# Enclosure_100x68_BPS.net
KiCad netlist of a schematic drawn in EAGLE
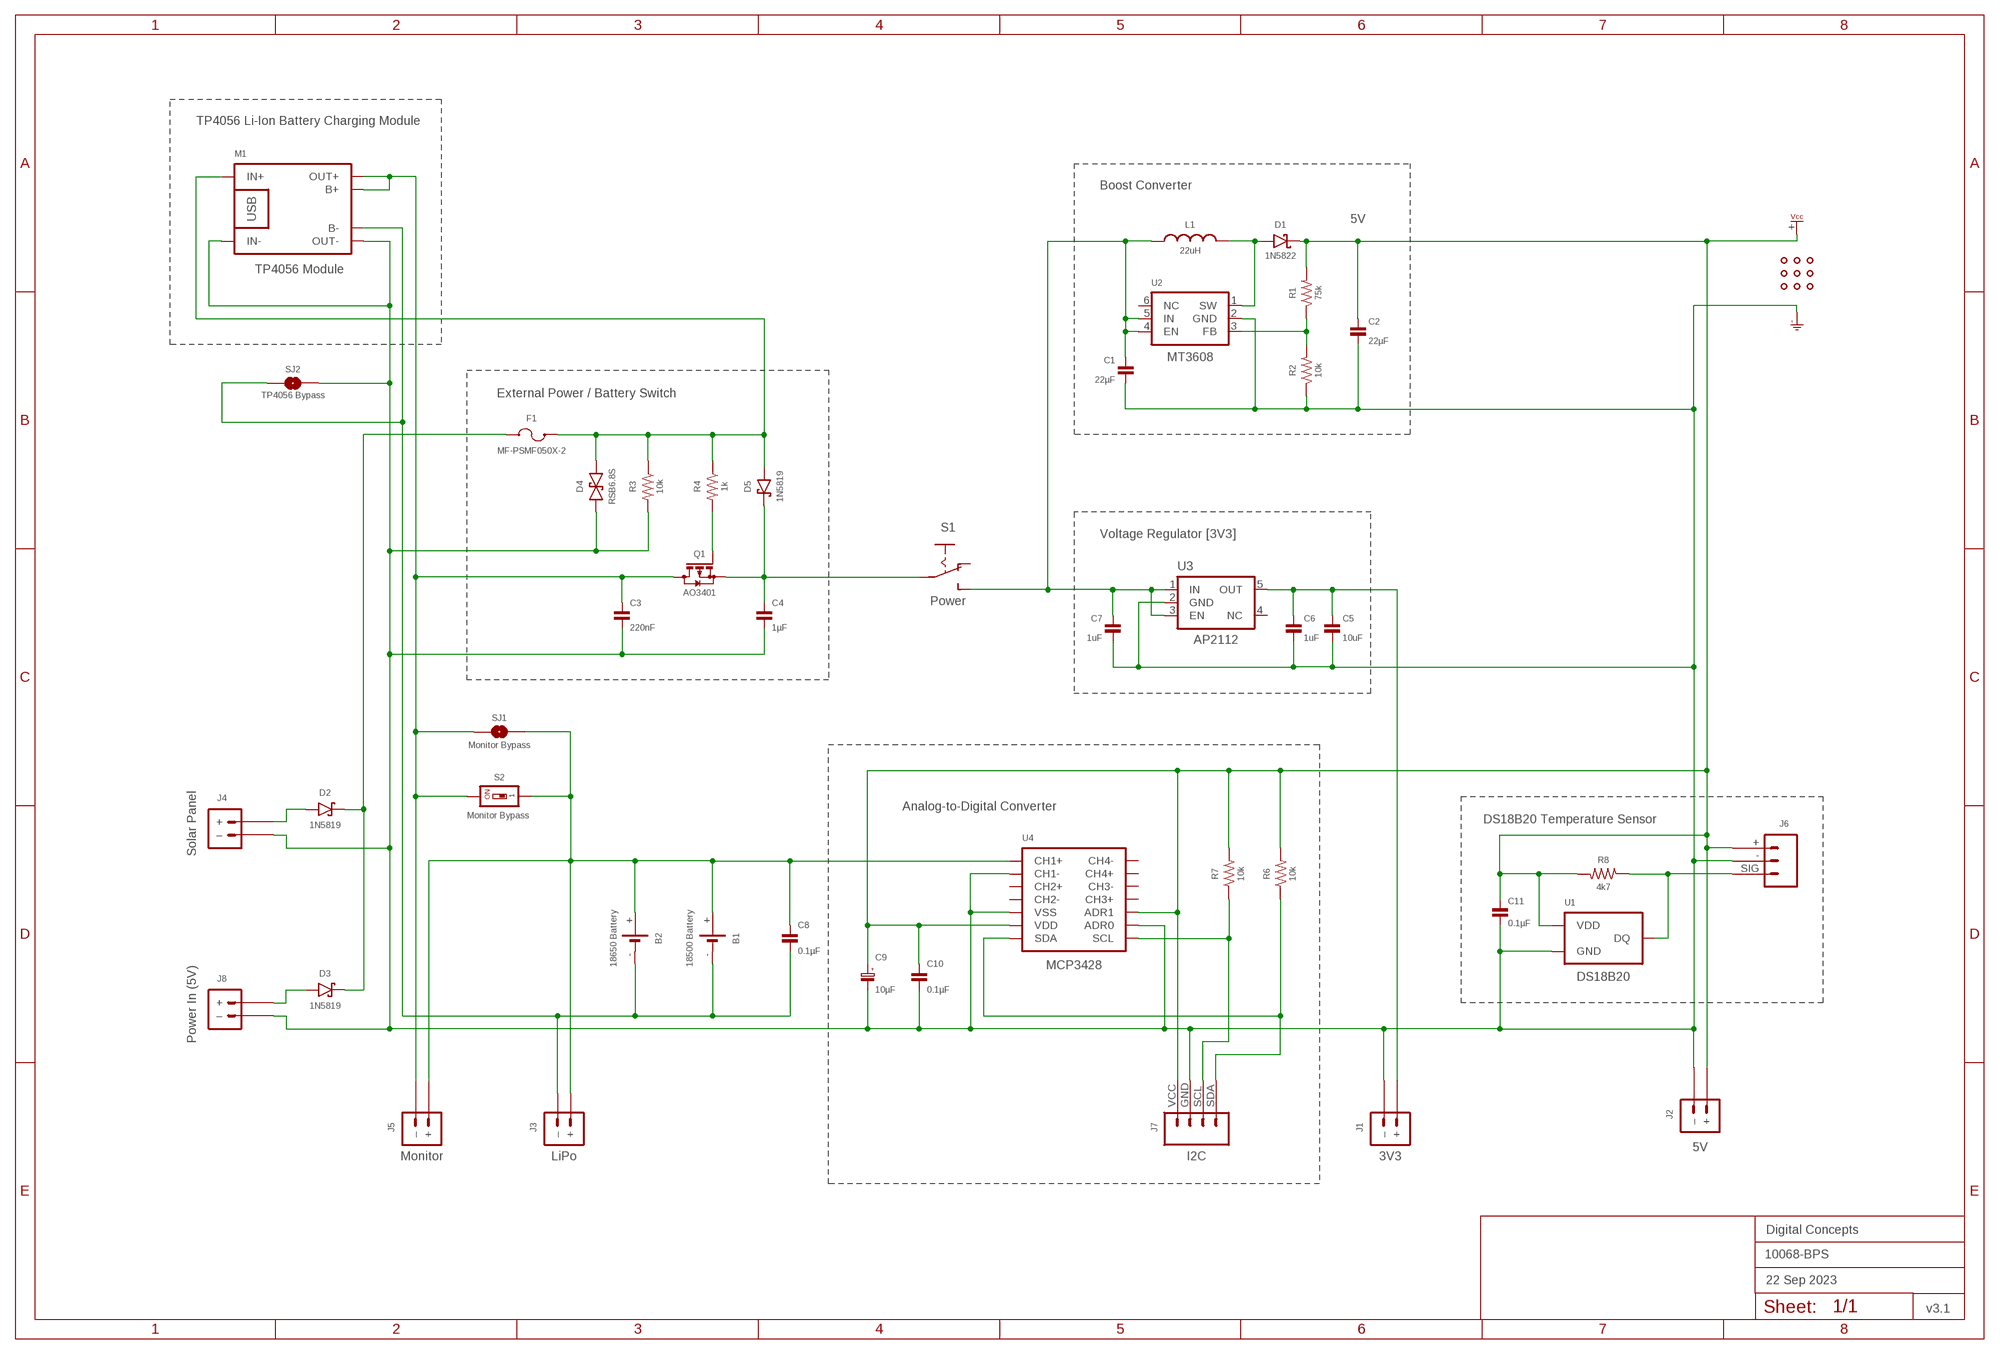
[diagram p0: schematic, sheet 1]

(export (version "E")
  (design (tool "Eeschema 10.0.6"))
  (components
    (comp (ref "B1")
      (value "18500 Battery")
      (footprint "eagle-import:BATTERY-18500")
      (libsource (lib "eagle-import") (part "BATTERY-HOLDER-18500"))
    )
    (comp (ref "B2")
      (value "18650 Battery")
      (footprint "eagle-import:BATTERY-18650")
      (libsource (lib "eagle-import") (part "BATTERY-HOLDER-18650"))
    )
    (comp (ref "C1")
      (value "22µF")
      (footprint "eagle-import:C1206")
      (libsource (lib "eagle-import") (part "CAPACITOR-1206"))
    )
    (comp (ref "C2")
      (value "22µF")
      (footprint "eagle-import:C1206")
      (libsource (lib "eagle-import") (part "CAPACITOR-1206"))
    )
    (comp (ref "C3")
      (value "220nF")
      (footprint "eagle-import:C0805")
      (libsource (lib "eagle-import") (part "CAPACITOR-0805"))
    )
    (comp (ref "C4")
      (value "1µF")
      (footprint "eagle-import:C0805")
      (libsource (lib "eagle-import") (part "CAPACITOR-0805"))
    )
    (comp (ref "C5")
      (value "10uF")
      (footprint "eagle-import:C0805")
      (libsource (lib "eagle-import") (part "CAPACITOR-0805"))
    )
    (comp (ref "C6")
      (value "1uF")
      (footprint "eagle-import:C0805")
      (libsource (lib "eagle-import") (part "CAPACITOR-0805"))
    )
    (comp (ref "C7")
      (value "1uF")
      (footprint "eagle-import:C0805")
      (libsource (lib "eagle-import") (part "CAPACITOR-0805"))
    )
    (comp (ref "C8")
      (value "0.1µF")
      (footprint "eagle-import:C0805")
      (libsource (lib "eagle-import") (part "CAPACITOR-0805"))
    )
    (comp (ref "C9")
      (value "10µF")
      (footprint "eagle-import:C1206-POLARISED")
      (libsource (lib "eagle-import") (part "CAPACITOR-1206-TANTALUM"))
    )
    (comp (ref "C10")
      (value "0.1µF")
      (footprint "eagle-import:C0805")
      (libsource (lib "eagle-import") (part "CAPACITOR-0805"))
    )
    (comp (ref "C11")
      (value "0.1µF")
      (footprint "eagle-import:C0805")
      (libsource (lib "eagle-import") (part "CAPACITOR-0805"))
    )
    (comp (ref "D1")
      (value "1N5822")
      (footprint "eagle-import:DIODE_SMB")
      (libsource (lib "eagle-import") (part "DIODE-SCHOTTKY-1N5822"))
    )
    (comp (ref "D2")
      (value "1N5819")
      (footprint "eagle-import:SOD-123")
      (libsource (lib "eagle-import") (part "DIODE-SCHOTTKY-1N5819"))
    )
    (comp (ref "D3")
      (value "1N5819")
      (footprint "eagle-import:SOD-123")
      (libsource (lib "eagle-import") (part "DIODE-SCHOTTKY-1N5819"))
    )
    (comp (ref "D4")
      (value "RSB6.8S")
      (footprint "eagle-import:EMD2")
      (libsource (lib "eagle-import") (part "DIODE-BIDIRECTIONAL-RSB6.8S"))
    )
    (comp (ref "D5")
      (value "1N5819")
      (footprint "eagle-import:SOD-123")
      (libsource (lib "eagle-import") (part "DIODE-SCHOTTKY-1N5819"))
    )
    (comp (ref "F1")
      (value "MF-PSMF050X-2")
      (footprint "eagle-import:F0805")
      (libsource (lib "eagle-import") (part "MF-PSMF050X-2"))
    )
    (comp (ref "J1")
      (value "3V3")
      (footprint "eagle-import:JST-PH2.0-2-VERTICAL-POWER")
      (libsource (lib "eagle-import") (part "JST-PH2.0-2-VERTICAL-POWER"))
    )
    (comp (ref "J2")
      (value "5V")
      (footprint "eagle-import:JST-PH2.0-2-VERTICAL-POWER")
      (libsource (lib "eagle-import") (part "JST-PH2.0-2-VERTICAL-POWER"))
    )
    (comp (ref "J3")
      (value "LiPo")
      (footprint "eagle-import:JST-PH2.0-2-HORIZONTAL-POWER")
      (libsource (lib "eagle-import") (part "JST-PH2.0-2-HORIZONTAL-POWERJST-PTH-2"))
    )
    (comp (ref "J4")
      (value "Solar Panel")
      (footprint "eagle-import:JST-PH2.0-2-VERTICAL-POWER")
      (libsource (lib "eagle-import") (part "JST-PH2.0-2-VERTICAL-POWER"))
    )
    (comp (ref "J5")
      (value "Monitor")
      (footprint "eagle-import:JST-PH2.0-2-VERTICAL-POWER")
      (libsource (lib "eagle-import") (part "JST-PH2.0-2-VERTICAL-POWER"))
    )
    (comp (ref "J6")
      (value "JST-PH2.0-3-HORIZONTAL-DS18B20")
      (footprint "eagle-import:JST-PH2.0-3-HORIZONTAL-DS18B20")
      (libsource (lib "eagle-import") (part "JST-PH2.0-3-HORIZONTAL-DS18B20"))
    )
    (comp (ref "J7")
      (value "I2C")
      (footprint "eagle-import:JST-PH2.0-4-HORIZONTAL-I2C")
      (libsource (lib "eagle-import") (part "JST-PH2.0-4-HORIZONTAL-I2C"))
    )
    (comp (ref "J8")
      (value "Power In (5V)")
      (footprint "eagle-import:JST-GH1.25-2-HORIZONTAL")
      (libsource (lib "eagle-import") (part "JST-GH1.25-2-HORIZONTAL-POWER"))
    )
    (comp (ref "L1")
      (value "22uH")
      (footprint "eagle-import:CDRH104R+")
      (libsource (lib "eagle-import") (part "INDUCTOR-CDRH104R+L5038P"))
    )
    (comp (ref "M1")
      (value "TP4056 Module")
      (footprint "eagle-import:BATTERY-CHARGER-LI-PROT")
      (libsource (lib "eagle-import") (part "BATTERY-CHARGER-LI-PROT"))
    )
    (comp (ref "Q1")
      (value "AO3401")
      (footprint "eagle-import:SOT-23")
      (libsource (lib "eagle-import") (part "MOSFET-AO3401"))
    )
    (comp (ref "R1")
      (value "75k")
      (footprint "eagle-import:R0805")
      (libsource (lib "eagle-import") (part "RESISTORR0805"))
    )
    (comp (ref "R2")
      (value "10k")
      (footprint "eagle-import:R0805")
      (libsource (lib "eagle-import") (part "RESISTORR0805"))
    )
    (comp (ref "R3")
      (value "10k")
      (footprint "eagle-import:R0805")
      (libsource (lib "eagle-import") (part "RESISTORR0805"))
    )
    (comp (ref "R4")
      (value "1k")
      (footprint "eagle-import:R0805")
      (libsource (lib "eagle-import") (part "RESISTORR0805"))
    )
    (comp (ref "R6")
      (value "10k")
      (footprint "eagle-import:R0805")
      (libsource (lib "eagle-import") (part "RESISTORR0805"))
    )
    (comp (ref "R7")
      (value "10k")
      (footprint "eagle-import:R0805")
      (libsource (lib "eagle-import") (part "RESISTORR0805"))
    )
    (comp (ref "R8")
      (value "4k7")
      (footprint "eagle-import:R0805")
      (libsource (lib "eagle-import") (part "RESISTORR0805"))
    )
    (comp (ref "S1")
      (value "Power")
      (footprint "eagle-import:SWITCH-SPDT-PTH")
      (libsource (lib "eagle-import") (part "SWITCH-SLIDE-SPDT-PTH"))
    )
    (comp (ref "S2")
      (value "Monitor Bypass")
      (footprint "eagle-import:SMD-001-VIA-1")
      (libsource (lib "eagle-import") (part "SWITCH-DIP-SWS001-VIA-1"))
    )
    (comp (ref "SJ1")
      (value "Monitor Bypass")
      (footprint "eagle-import:SJ")
      (libsource (lib "eagle-import") (part "SJ"))
    )
    (comp (ref "SJ2")
      (value "TP4056 Bypass")
      (footprint "eagle-import:SJ")
      (libsource (lib "eagle-import") (part "SJ"))
    )
    (comp (ref "U$1")
      (value "PROTO-34X22-PI-CUT")
      (footprint "eagle-import:PROTO-34X22-PI-CUT")
      (libsource (lib "eagle-import") (part "PROTO-34X22-PI-CUT"))
    )
    (comp (ref "U1")
      (value "DS18B20")
      (footprint "eagle-import:TO-92")
      (fields (field (name "MF") "Maxim Integrated"))
      (libsource (lib "eagle-import") (part "THERMOMETER-DS18B20"))
    )
    (comp (ref "U2")
      (value "MT3608")
      (footprint "eagle-import:SOT-23-6")
      (libsource (lib "eagle-import") (part "MT3608"))
    )
    (comp (ref "U3")
      (value "AP2112")
      (footprint "eagle-import:SOT25")
      (libsource (lib "eagle-import") (part "REGULATOR-AP2112"))
    )
    (comp (ref "U4")
      (value "MCP3428")
      (footprint "eagle-import:SOIC-14")
      (libsource (lib "eagle-import") (part "MCP3428"))
    )
  )
  (nets
    (net (code "1") (name "Net-(C9-+)") (class "Default")
      (node (ref "C10") (pin "1") (pinfunction "1_1") (pintype "passive"))
      (node (ref "C11") (pin "1") (pinfunction "1_1") (pintype "passive"))
      (node (ref "C2") (pin "1") (pinfunction "1_1") (pintype "passive"))
      (node (ref "C9") (pin "1") (pinfunction "+_1") (pintype "passive"))
      (node (ref "D1") (pin "C") (pinfunction "C_C") (pintype "passive"))
      (node (ref "J2") (pin "+") (pinfunction "+_+") (pintype "power_in"))
      (node (ref "J6") (pin "+") (pinfunction "3_+") (pintype "passive"))
      (node (ref "J7") (pin "VCC") (pinfunction "1_VCC") (pintype "passive"))
      (node (ref "R1") (pin "2") (pinfunction "2_2") (pintype "passive"))
      (node (ref "R6") (pin "2") (pinfunction "2_2") (pintype "passive"))
      (node (ref "R7") (pin "2") (pinfunction "2_2") (pintype "passive"))
      (node (ref "R8") (pin "2") (pinfunction "2_2") (pintype "passive"))
      (node (ref "U$1") (pin "+") (pinfunction "VCC_+") (pintype "power_in"))
      (node (ref "U1") (pin "3") (pinfunction "VDD_3") (pintype "power_in"))
      (node (ref "U4") (pin "P$10") (pinfunction "ADR1_P$10") (pintype "bidirectional"))
      (node (ref "U4") (pin "P$6") (pinfunction "VDD_P$6") (pintype "bidirectional"))
    )
    (net (code "2") (name "Net-(C9--)") (class "Default")
      (node (ref "C1") (pin "2") (pinfunction "2_2") (pintype "passive"))
      (node (ref "C10") (pin "2") (pinfunction "2_2") (pintype "passive"))
      (node (ref "C11") (pin "2") (pinfunction "2_2") (pintype "passive"))
      (node (ref "C2") (pin "2") (pinfunction "2_2") (pintype "passive"))
      (node (ref "C3") (pin "2") (pinfunction "2_2") (pintype "passive"))
      (node (ref "C4") (pin "2") (pinfunction "2_2") (pintype "passive"))
      (node (ref "C5") (pin "2") (pinfunction "2_2") (pintype "passive"))
      (node (ref "C6") (pin "2") (pinfunction "2_2") (pintype "passive"))
      (node (ref "C7") (pin "2") (pinfunction "2_2") (pintype "passive"))
      (node (ref "C9") (pin "2") (pinfunction "-_2") (pintype "passive"))
      (node (ref "D4") (pin "P$2") (pinfunction "2_P$2") (pintype "passive"))
      (node (ref "J1") (pin "-") (pinfunction "–_-") (pintype "power_in"))
      (node (ref "J2") (pin "-") (pinfunction "–_-") (pintype "power_in"))
      (node (ref "J4") (pin "-") (pinfunction "–_-") (pintype "power_in"))
      (node (ref "J6") (pin "-") (pinfunction "2_-") (pintype "passive"))
      (node (ref "J7") (pin "GND") (pinfunction "2_GND") (pintype "passive"))
      (node (ref "J8") (pin "-") (pinfunction "–_-") (pintype "power_in"))
      (node (ref "M1") (pin "IN-") (pinfunction "IN-_IN-") (pintype "power_in"))
      (node (ref "M1") (pin "OUT-") (pinfunction "OUT-_OUT-") (pintype "power_in"))
      (node (ref "R2") (pin "1") (pinfunction "1_1") (pintype "passive"))
      (node (ref "R3") (pin "2") (pinfunction "2_2") (pintype "passive"))
      (node (ref "SJ2") (pin "1") (pinfunction "1_1") (pintype "passive"))
      (node (ref "U$1") (pin "-") (pinfunction "GND_-") (pintype "power_in"))
      (node (ref "U1") (pin "1") (pinfunction "GND_1") (pintype "power_in"))
      (node (ref "U2") (pin "2") (pinfunction "GND_2") (pintype "power_in"))
      (node (ref "U3") (pin "2") (pinfunction "GND_2") (pintype "power_in"))
      (node (ref "U4") (pin "P$2") (pinfunction "CH1-_P$2") (pintype "bidirectional"))
      (node (ref "U4") (pin "P$5") (pinfunction "VSS_P$5") (pintype "bidirectional"))
      (node (ref "U4") (pin "P$9") (pinfunction "ADR0_P$9") (pintype "bidirectional"))
    )
    (net (code "3") (name "Net-(D2-PadA)") (class "Default")
      (node (ref "D2") (pin "A") (pinfunction "A_A") (pintype "passive"))
      (node (ref "J4") (pin "+") (pinfunction "+_+") (pintype "power_in"))
    )
    (net (code "4") (name "Net-(D2-PadC)") (class "Default")
      (node (ref "D2") (pin "C") (pinfunction "C_C") (pintype "passive"))
      (node (ref "D3") (pin "C") (pinfunction "C_C") (pintype "passive"))
      (node (ref "F1") (pin "1") (pinfunction "1_1") (pintype "passive"))
    )
    (net (code "5") (name "Net-(D3-PadA)") (class "Default")
      (node (ref "D3") (pin "A") (pinfunction "A_A") (pintype "passive"))
      (node (ref "J8") (pin "+") (pinfunction "+_+") (pintype "power_in"))
    )
    (net (code "6") (name "Net-(D4-1)") (class "Default")
      (node (ref "D4") (pin "P$1") (pinfunction "1_P$1") (pintype "passive"))
      (node (ref "D5") (pin "A") (pinfunction "A_A") (pintype "passive"))
      (node (ref "F1") (pin "2") (pinfunction "2_2") (pintype "passive"))
      (node (ref "M1") (pin "IN+") (pinfunction "IN+_IN+") (pintype "power_in"))
      (node (ref "R3") (pin "1") (pinfunction "1_1") (pintype "passive"))
      (node (ref "R4") (pin "1") (pinfunction "1_1") (pintype "passive"))
    )
    (net (code "7") (name "Net-(J3-–)") (class "Default")
      (node (ref "B1") (pin "-") (pinfunction "-_-") (pintype "power_in"))
      (node (ref "B2") (pin "-") (pinfunction "-_-") (pintype "power_in"))
      (node (ref "C8") (pin "2") (pinfunction "2_2") (pintype "passive"))
      (node (ref "J3") (pin "-") (pinfunction "–_-") (pintype "power_in"))
      (node (ref "M1") (pin "B-") (pinfunction "B-_B-") (pintype "power_in"))
      (node (ref "SJ2") (pin "2") (pinfunction "2_2") (pintype "passive"))
    )
    (net (code "8") (name "Net-(J5-–)") (class "Default")
      (node (ref "C3") (pin "1") (pinfunction "1_1") (pintype "passive"))
      (node (ref "J5") (pin "-") (pinfunction "–_-") (pintype "power_in"))
      (node (ref "M1") (pin "B+") (pinfunction "B+_B+") (pintype "power_in"))
      (node (ref "M1") (pin "OUT+") (pinfunction "OUT+_OUT+") (pintype "power_in"))
      (node (ref "Q1") (pin "3") (pinfunction "D_3") (pintype "passive"))
      (node (ref "S2") (pin "2") (pinfunction "2_2") (pintype "passive"))
      (node (ref "SJ1") (pin "2") (pinfunction "2_2") (pintype "passive"))
    )
    (net (code "9") (name "Net-(J6-1)") (class "Default")
      (node (ref "J6") (pin "SIG") (pinfunction "1_SIG") (pintype "passive"))
      (node (ref "R8") (pin "1") (pinfunction "1_1") (pintype "passive"))
      (node (ref "U1") (pin "2") (pinfunction "DQ_2") (pintype "bidirectional"))
    )
    (net (code "10") (name "Net-(J7-3)") (class "Default")
      (node (ref "J7") (pin "SCL") (pinfunction "3_SCL") (pintype "passive"))
      (node (ref "R7") (pin "1") (pinfunction "1_1") (pintype "passive"))
      (node (ref "U4") (pin "P$8") (pinfunction "SCL_P$8") (pintype "bidirectional"))
    )
    (net (code "11") (name "Net-(J7-4)") (class "Default")
      (node (ref "J7") (pin "SDA") (pinfunction "4_SDA") (pintype "passive"))
      (node (ref "R6") (pin "1") (pinfunction "1_1") (pintype "passive"))
      (node (ref "U4") (pin "P$7") (pinfunction "SDA_P$7") (pintype "bidirectional"))
    )
    (net (code "12") (name "Net-(Q1-G)") (class "Default")
      (node (ref "Q1") (pin "1") (pinfunction "G_1") (pintype "passive"))
      (node (ref "R4") (pin "2") (pinfunction "2_2") (pintype "passive"))
    )
    (net (code "13") (name "Net-(Q1-S)") (class "Default")
      (node (ref "C4") (pin "1") (pinfunction "1_1") (pintype "passive"))
      (node (ref "D5") (pin "C") (pinfunction "C_C") (pintype "passive"))
      (node (ref "Q1") (pin "2") (pinfunction "S_2") (pintype "passive"))
      (node (ref "S1") (pin "2") (pinfunction "P_2") (pintype "passive"))
    )
    (net (code "14") (name "Net-(S1-S)") (class "Default")
      (node (ref "C1") (pin "1") (pinfunction "1_1") (pintype "passive"))
      (node (ref "C7") (pin "1") (pinfunction "1_1") (pintype "passive"))
      (node (ref "L1") (pin "2") (pinfunction "2_2") (pintype "passive"))
      (node (ref "S1") (pin "3") (pinfunction "S_3") (pintype "passive"))
      (node (ref "U2") (pin "4") (pinfunction "EN_4") (pintype "input"))
      (node (ref "U2") (pin "5") (pinfunction "IN_5") (pintype "power_in"))
      (node (ref "U3") (pin "1") (pinfunction "IN_1") (pintype "power_in"))
      (node (ref "U3") (pin "3") (pinfunction "EN_3") (pintype "input"))
    )
    (net (code "15") (name "Net-(U2-FB)") (class "Default")
      (node (ref "R1") (pin "1") (pinfunction "1_1") (pintype "passive"))
      (node (ref "R2") (pin "2") (pinfunction "2_2") (pintype "passive"))
      (node (ref "U2") (pin "3") (pinfunction "FB_3") (pintype "input"))
    )
    (net (code "16") (name "Net-(U2-SW)") (class "Default")
      (node (ref "D1") (pin "A") (pinfunction "A_A") (pintype "passive"))
      (node (ref "L1") (pin "1") (pinfunction "1_1") (pintype "passive"))
      (node (ref "U2") (pin "1") (pinfunction "SW_1") (pintype "power_in"))
    )
    (net (code "17") (name "Net-(U3-OUT)") (class "Default")
      (node (ref "C5") (pin "1") (pinfunction "1_1") (pintype "passive"))
      (node (ref "C6") (pin "1") (pinfunction "1_1") (pintype "passive"))
      (node (ref "J1") (pin "+") (pinfunction "+_+") (pintype "power_in"))
      (node (ref "U3") (pin "5") (pinfunction "OUT_5") (pintype "power_in"))
    )
    (net (code "18") (name "Net-(U4-CH1+)") (class "Default")
      (node (ref "B1") (pin "+") (pinfunction "+_+") (pintype "power_in"))
      (node (ref "B2") (pin "+") (pinfunction "+_+") (pintype "power_in"))
      (node (ref "C8") (pin "1") (pinfunction "1_1") (pintype "passive"))
      (node (ref "J3") (pin "+") (pinfunction "+_+") (pintype "power_in"))
      (node (ref "J5") (pin "+") (pinfunction "+_+") (pintype "power_in"))
      (node (ref "S2") (pin "1") (pinfunction "1_1") (pintype "passive"))
      (node (ref "S2") (pin "1@VIA") (pinfunction "1_1@VIA") (pintype "passive"))
      (node (ref "SJ1") (pin "1") (pinfunction "1_1") (pintype "passive"))
      (node (ref "U4") (pin "P$1") (pinfunction "CH1+_P$1") (pintype "bidirectional"))
    )
    (net (code "19") (name "unconnected-(S1-O-Pad1)") (class "Default")
      (node (ref "S1") (pin "1") (pinfunction "O_1") (pintype "passive"))
    )
    (net (code "20") (name "unconnected-(U2-NC-Pad6)") (class "Default")
      (node (ref "U2") (pin "6") (pinfunction "NC_6") (pintype "no_connect"))
    )
    (net (code "21") (name "unconnected-(U3-NC-Pad4)") (class "Default")
      (node (ref "U3") (pin "4") (pinfunction "NC_4") (pintype "no_connect"))
    )
    (net (code "22") (name "unconnected-(U4-CH2+-PadP$3)") (class "Default")
      (node (ref "U4") (pin "P$3") (pinfunction "CH2+_P$3") (pintype "bidirectional"))
    )
    (net (code "23") (name "unconnected-(U4-CH2--PadP$4)") (class "Default")
      (node (ref "U4") (pin "P$4") (pinfunction "CH2-_P$4") (pintype "bidirectional"))
    )
    (net (code "24") (name "unconnected-(U4-CH3+-PadP$11)") (class "Default")
      (node (ref "U4") (pin "P$11") (pinfunction "CH3+_P$11") (pintype "bidirectional"))
    )
    (net (code "25") (name "unconnected-(U4-CH3--PadP$12)") (class "Default")
      (node (ref "U4") (pin "P$12") (pinfunction "CH3-_P$12") (pintype "bidirectional"))
    )
    (net (code "26") (name "unconnected-(U4-CH4+-PadP$13)") (class "Default")
      (node (ref "U4") (pin "P$13") (pinfunction "CH4+_P$13") (pintype "bidirectional"))
    )
    (net (code "27") (name "unconnected-(U4-CH4--PadP$14)") (class "Default")
      (node (ref "U4") (pin "P$14") (pinfunction "CH4-_P$14") (pintype "bidirectional"))
    )
  )
)
